# Sheet2.net
KiCad netlist of a schematic drawn in Altium Designer
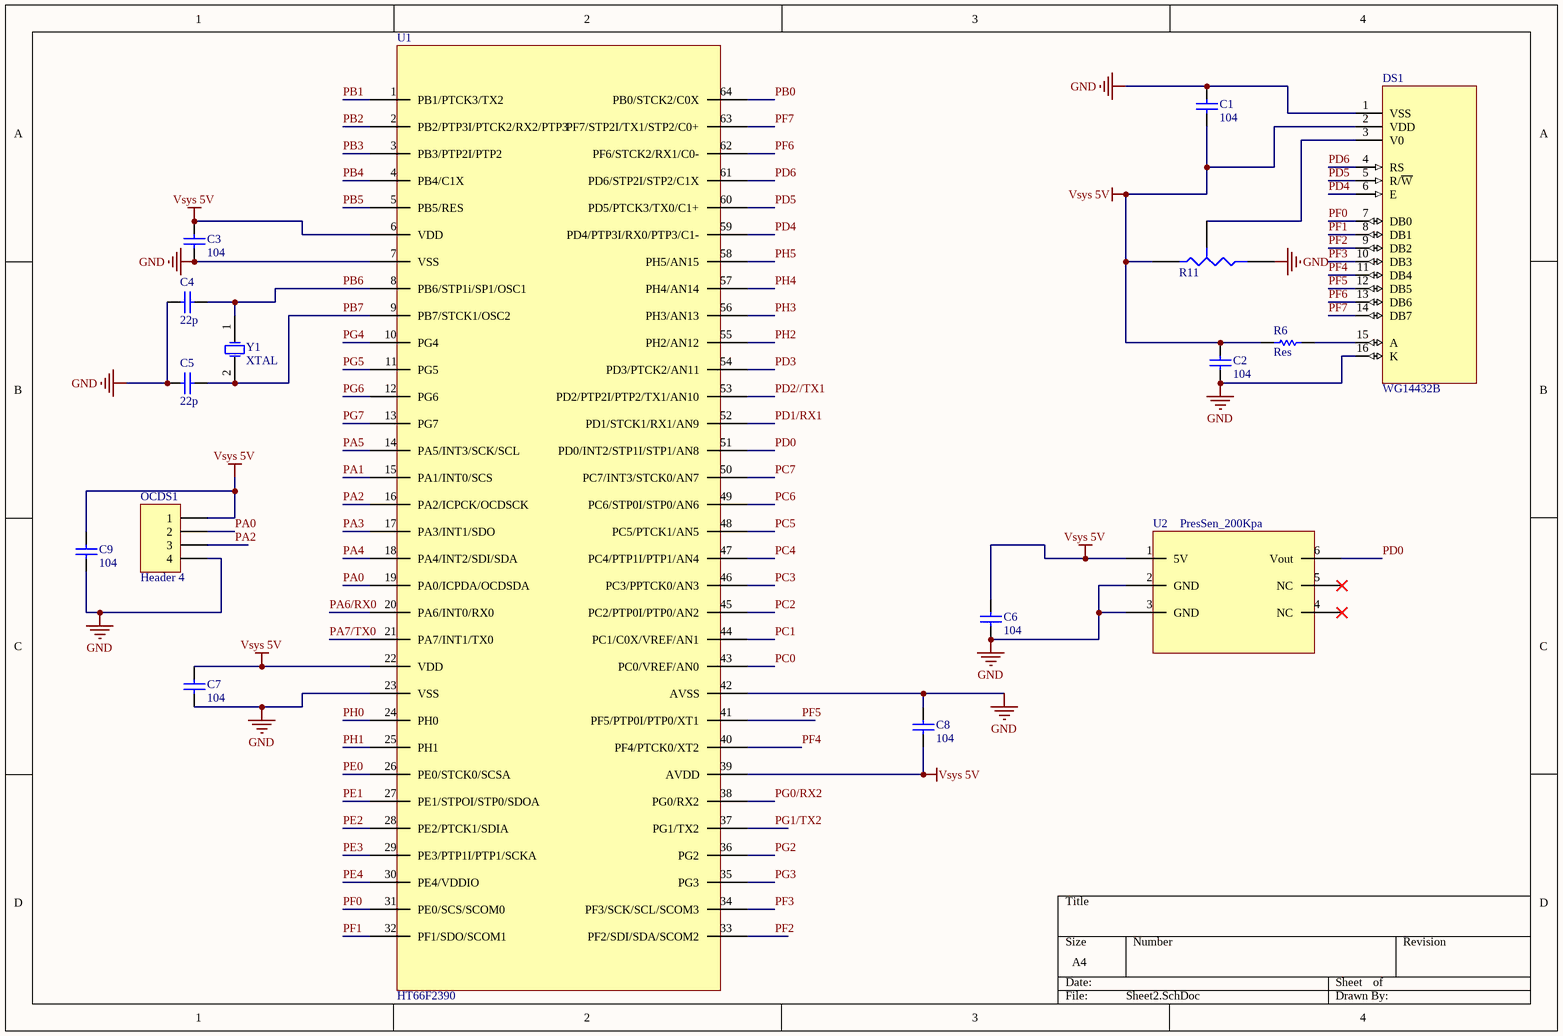
[diagram p0: Sheet2.SchDoc]

(export (version "E")
  (design (tool "Eeschema 10.0.6"))
  (components
    (comp (ref "C1")
      (value "104")
      (footprint "C200")
      (description "Capacitor")
      (fields (field (name "PUBLISHER") "Altium Limited"))
      (libsource (lib "myLib2009") (part "Cap"))
    )
    (comp (ref "C2")
      (value "104")
      (footprint "C200")
      (description "Capacitor")
      (fields (field (name "PUBLISHER") "Altium Limited"))
      (libsource (lib "myLib2009") (part "Cap"))
    )
    (comp (ref "C3")
      (value "104")
      (footprint "C200")
      (description "Capacitor")
      (fields (field (name "PUBLISHER") "Altium Limited"))
      (libsource (lib "myLib2009") (part "Cap"))
    )
    (comp (ref "C4")
      (value "22p")
      (footprint "C200")
      (description "Capacitor")
      (fields (field (name "PUBLISHER") "Altium Limited"))
      (libsource (lib "myLib2009") (part "Cap"))
    )
    (comp (ref "C5")
      (value "22p")
      (footprint "C200")
      (description "Capacitor")
      (fields (field (name "PUBLISHER") "Altium Limited"))
      (libsource (lib "myLib2009") (part "Cap"))
    )
    (comp (ref "C6")
      (value "104")
      (footprint "C200")
      (description "Capacitor")
      (fields (field (name "PUBLISHER") "Altium Limited"))
      (libsource (lib "myLib2009") (part "Cap"))
    )
    (comp (ref "C7")
      (value "104")
      (footprint "C200")
      (description "Capacitor")
      (fields (field (name "PUBLISHER") "Altium Limited"))
      (libsource (lib "myLib2009") (part "Cap"))
    )
    (comp (ref "C8")
      (value "104")
      (footprint "C200")
      (description "Capacitor")
      (fields (field (name "PUBLISHER") "Altium Limited"))
      (libsource (lib "myLib2009") (part "Cap"))
    )
    (comp (ref "C9")
      (value "104")
      (footprint "C200")
      (description "Capacitor")
      (fields (field (name "PUBLISHER") "Altium Limited"))
      (libsource (lib "myLib2009") (part "Cap"))
    )
    (comp (ref "DS1")
      (value "WG14432B")
      (footprint "LCM_16")
      (description "LCD Module")
      (libsource (lib "myLib2009") (part "WG14432B"))
    )
    (comp (ref "OCDS1")
      (value "Header 4")
      (footprint "HDR1X4")
      (description "Header, 4-Pin")
      (fields (field (name "PUBLISHER") "Altium Limited"))
      (libsource (lib "Miscellaneous Connectors") (part "Header 4"))
    )
    (comp (ref "R6")
      (value "Res")
      (footprint "AXIAL-0.3")
      (description "Resistor")
      (fields (field (name "PUBLISHER") "Altium Limited"))
      (libsource (lib "myLib2009") (part "Res"))
    )
    (comp (ref "R11")
      (value "Res Tap")
      (footprint "VR3")
      (description "Tapped Resistor")
      (fields (field (name "PUBLISHER") "Altium Limited"))
      (libsource (lib "Miscellaneous Devices") (part "Res Tap"))
    )
    (comp (ref "U1") (value "HT66F2390") (footprint "LFPQ-64") (libsource (lib "0612") (part "HT66F2390")))
    (comp (ref "U2")
      (value "PresSen_200Kpa")
      (footprint "RSCM17100Kxxxx")
      (libsource (lib "0612") (part "PresSen_200Kpa"))
    )
    (comp (ref "Y1")
      (value "XTAL")
      (footprint "XTAL4-8")
      (description "Crystal Oscillator")
      (fields (field (name "PUBLISHER") "Altium Limited"))
      (libsource (lib "myLib2009") (part "XTAL"))
    )
  )
  (nets
    (net (code "1") (name "/PA0") (class "Default")
      (node (ref "OCDS1") (pin "2") (pinfunction "2_2") (pintype "passive"))
      (node (ref "U1") (pin "19") (pinfunction "PA0/ICPDA/OCDSDA_19") (pintype "passive"))
    )
    (net (code "2") (name "/PA1") (class "Default")
      (node (ref "U1") (pin "15") (pinfunction "PA1/INT0/SCS_15") (pintype "passive"))
    )
    (net (code "3") (name "/PA2") (class "Default")
      (node (ref "OCDS1") (pin "3") (pinfunction "3_3") (pintype "passive"))
      (node (ref "U1") (pin "16") (pinfunction "PA2/ICPCK/OCDSCK_16") (pintype "passive"))
    )
    (net (code "4") (name "/PA3") (class "Default")
      (node (ref "U1") (pin "17") (pinfunction "PA3/INT1/SDO_17") (pintype "passive"))
    )
    (net (code "5") (name "/PA4") (class "Default")
      (node (ref "U1") (pin "18") (pinfunction "PA4/INT2/SDI/SDA_18") (pintype "passive"))
    )
    (net (code "6") (name "/PA5") (class "Default")
      (node (ref "U1") (pin "14") (pinfunction "PA5/INT3/SCK/SCL_14") (pintype "passive"))
    )
    (net (code "7") (name "/PA6{slash}RX0") (class "Default")
      (node (ref "U1") (pin "20") (pinfunction "PA6/INT0/RX0_20") (pintype "passive"))
    )
    (net (code "8") (name "/PA7{slash}TX0") (class "Default")
      (node (ref "U1") (pin "21") (pinfunction "PA7/INT1/TX0_21") (pintype "passive"))
    )
    (net (code "9") (name "/PB0") (class "Default")
      (node (ref "U1") (pin "64") (pinfunction "PB0/STCK2/C0X_64") (pintype "passive"))
    )
    (net (code "10") (name "/PB1") (class "Default")
      (node (ref "U1") (pin "1") (pinfunction "PB1/PTCK3/TX2_1") (pintype "passive"))
    )
    (net (code "11") (name "/PB2") (class "Default")
      (node (ref "U1") (pin "2") (pinfunction "PB2/PTP3I/PTCK2/RX2/PTP3_2") (pintype "passive"))
    )
    (net (code "12") (name "/PB3") (class "Default")
      (node (ref "U1") (pin "3") (pinfunction "PB3/PTP2I/PTP2_3") (pintype "passive"))
    )
    (net (code "13") (name "/PB4") (class "Default")
      (node (ref "U1") (pin "4") (pinfunction "PB4/C1X_4") (pintype "passive"))
    )
    (net (code "14") (name "/PB5") (class "Default")
      (node (ref "U1") (pin "5") (pinfunction "PB5/RES_5") (pintype "passive"))
    )
    (net (code "15") (name "/PB6") (class "Default")
      (node (ref "C4") (pin "2") (pinfunction "2_2") (pintype "passive"))
      (node (ref "U1") (pin "8") (pinfunction "PB6/STP1i/SP1/OSC1_8") (pintype "passive"))
      (node (ref "Y1") (pin "1") (pinfunction "OSC1_1") (pintype "passive"))
    )
    (net (code "16") (name "/PB7") (class "Default")
      (node (ref "C5") (pin "2") (pinfunction "2_2") (pintype "passive"))
      (node (ref "U1") (pin "9") (pinfunction "PB7/STCK1/OSC2_9") (pintype "passive"))
      (node (ref "Y1") (pin "2") (pinfunction "OSC2_2") (pintype "passive"))
    )
    (net (code "17") (name "/PC0") (class "Default")
      (node (ref "U1") (pin "43") (pinfunction "PC0/VREF/AN0_43") (pintype "passive"))
    )
    (net (code "18") (name "/PC1") (class "Default")
      (node (ref "U1") (pin "44") (pinfunction "PC1/C0X/VREF/AN1_44") (pintype "passive"))
    )
    (net (code "19") (name "/PC2") (class "Default")
      (node (ref "U1") (pin "45") (pinfunction "PC2/PTP0I/PTP0/AN2_45") (pintype "passive"))
    )
    (net (code "20") (name "/PC3") (class "Default")
      (node (ref "U1") (pin "46") (pinfunction "PC3/PPTCK0/AN3_46") (pintype "passive"))
    )
    (net (code "21") (name "/PC4") (class "Default")
      (node (ref "U1") (pin "47") (pinfunction "PC4/PTP1I/PTP1/AN4_47") (pintype "passive"))
    )
    (net (code "22") (name "/PC5") (class "Default")
      (node (ref "U1") (pin "48") (pinfunction "PC5/PTCK1/AN5_48") (pintype "passive"))
    )
    (net (code "23") (name "/PC6") (class "Default")
      (node (ref "U1") (pin "49") (pinfunction "PC6/STP0I/STP0/AN6_49") (pintype "passive"))
    )
    (net (code "24") (name "/PC7") (class "Default")
      (node (ref "U1") (pin "50") (pinfunction "PC7/INT3/STCK0/AN7_50") (pintype "passive"))
    )
    (net (code "25") (name "/PD0") (class "Default")
      (node (ref "U1") (pin "51") (pinfunction "PD0/INT2/STP1I/STP1/AN8_51") (pintype "passive"))
      (node (ref "U2") (pin "6") (pinfunction "Vout_6") (pintype "passive"))
    )
    (net (code "26") (name "/PD1{slash}RX1") (class "Default")
      (node (ref "U1") (pin "52") (pinfunction "PD1/STCK1/RX1/AN9_52") (pintype "passive"))
    )
    (net (code "27") (name "/PD2{slash}{slash}TX1") (class "Default")
      (node (ref "U1") (pin "53") (pinfunction "PD2/PTP2I/PTP2/TX1/AN10_53") (pintype "passive"))
    )
    (net (code "28") (name "/PD3") (class "Default")
      (node (ref "U1") (pin "54") (pinfunction "PD3/PTCK2/AN11_54") (pintype "passive"))
    )
    (net (code "29") (name "/PD4") (class "Default")
      (node (ref "DS1") (pin "6") (pinfunction "E_6") (pintype "input"))
      (node (ref "U1") (pin "59") (pinfunction "PD4/PTP3I/RX0/PTP3/C1-_59") (pintype "passive"))
    )
    (net (code "30") (name "/PD5") (class "Default")
      (node (ref "DS1") (pin "5") (pinfunction "R/~{W}_5") (pintype "input"))
      (node (ref "U1") (pin "60") (pinfunction "PD5/PTCK3/TX0/C1+_60") (pintype "passive"))
    )
    (net (code "31") (name "/PD6") (class "Default")
      (node (ref "DS1") (pin "4") (pinfunction "RS_4") (pintype "input"))
      (node (ref "U1") (pin "61") (pinfunction "PD6/STP2I/STP2/C1X_61") (pintype "passive"))
    )
    (net (code "32") (name "/PE0") (class "Default")
      (node (ref "U1") (pin "26") (pinfunction "PE0/STCK0/SCSA_26") (pintype "passive"))
    )
    (net (code "33") (name "/PE1") (class "Default")
      (node (ref "U1") (pin "27") (pinfunction "PE1/STPOI/STP0/SDOA_27") (pintype "passive"))
    )
    (net (code "34") (name "/PE2") (class "Default")
      (node (ref "U1") (pin "28") (pinfunction "PE2/PTCK1/SDIA_28") (pintype "passive"))
    )
    (net (code "35") (name "/PE3") (class "Default")
      (node (ref "U1") (pin "29") (pinfunction "PE3/PTP1I/PTP1/SCKA_29") (pintype "passive"))
    )
    (net (code "36") (name "/PE4") (class "Default")
      (node (ref "U1") (pin "30") (pinfunction "PE4/VDDIO_30") (pintype "passive"))
    )
    (net (code "37") (name "/PF0") (class "Default")
      (node (ref "DS1") (pin "7") (pinfunction "DB0_7") (pintype "bidirectional"))
      (node (ref "U1") (pin "31") (pinfunction "PE0/SCS/SCOM0_31") (pintype "passive"))
    )
    (net (code "38") (name "/PF1") (class "Default")
      (node (ref "DS1") (pin "8") (pinfunction "DB1_8") (pintype "bidirectional"))
      (node (ref "U1") (pin "32") (pinfunction "PF1/SDO/SCOM1_32") (pintype "passive"))
    )
    (net (code "39") (name "/PF2") (class "Default")
      (node (ref "DS1") (pin "9") (pinfunction "DB2_9") (pintype "bidirectional"))
      (node (ref "U1") (pin "33") (pinfunction "PF2/SDI/SDA/SCOM2_33") (pintype "passive"))
    )
    (net (code "40") (name "/PF3") (class "Default")
      (node (ref "DS1") (pin "10") (pinfunction "DB3_10") (pintype "bidirectional"))
      (node (ref "U1") (pin "34") (pinfunction "PF3/SCK/SCL/SCOM3_34") (pintype "passive"))
    )
    (net (code "41") (name "/PF4") (class "Default")
      (node (ref "DS1") (pin "11") (pinfunction "DB4_11") (pintype "bidirectional"))
      (node (ref "U1") (pin "40") (pinfunction "PF4/PTCK0/XT2_40") (pintype "passive"))
    )
    (net (code "42") (name "/PF5") (class "Default")
      (node (ref "DS1") (pin "12") (pinfunction "DB5_12") (pintype "bidirectional"))
      (node (ref "U1") (pin "41") (pinfunction "PF5/PTP0I/PTP0/XT1_41") (pintype "passive"))
    )
    (net (code "43") (name "/PF6") (class "Default")
      (node (ref "DS1") (pin "13") (pinfunction "DB6_13") (pintype "bidirectional"))
      (node (ref "U1") (pin "62") (pinfunction "PF6/STCK2/RX1/C0-_62") (pintype "passive"))
    )
    (net (code "44") (name "/PF7") (class "Default")
      (node (ref "DS1") (pin "14") (pinfunction "DB7_14") (pintype "bidirectional"))
      (node (ref "U1") (pin "63") (pinfunction "PF7/STP2I/TX1/STP2/C0+_63") (pintype "passive"))
    )
    (net (code "45") (name "/PG0{slash}RX2") (class "Default")
      (node (ref "U1") (pin "38") (pinfunction "PG0/RX2_38") (pintype "passive"))
    )
    (net (code "46") (name "/PG1{slash}TX2") (class "Default")
      (node (ref "U1") (pin "37") (pinfunction "PG1/TX2_37") (pintype "passive"))
    )
    (net (code "47") (name "/PG2") (class "Default")
      (node (ref "U1") (pin "36") (pinfunction "PG2_36") (pintype "passive"))
    )
    (net (code "48") (name "/PG3") (class "Default")
      (node (ref "U1") (pin "35") (pinfunction "PG3_35") (pintype "passive"))
    )
    (net (code "49") (name "/PG4") (class "Default")
      (node (ref "U1") (pin "10") (pinfunction "PG4_10") (pintype "passive"))
    )
    (net (code "50") (name "/PG5") (class "Default")
      (node (ref "U1") (pin "11") (pinfunction "PG5_11") (pintype "passive"))
    )
    (net (code "51") (name "/PG6") (class "Default")
      (node (ref "U1") (pin "12") (pinfunction "PG6_12") (pintype "passive"))
    )
    (net (code "52") (name "/PG7") (class "Default")
      (node (ref "U1") (pin "13") (pinfunction "PG7_13") (pintype "passive"))
    )
    (net (code "53") (name "/PH0") (class "Default")
      (node (ref "U1") (pin "24") (pinfunction "PH0_24") (pintype "passive"))
    )
    (net (code "54") (name "/PH1") (class "Default")
      (node (ref "U1") (pin "25") (pinfunction "PH1_25") (pintype "passive"))
    )
    (net (code "55") (name "/PH2") (class "Default")
      (node (ref "U1") (pin "55") (pinfunction "PH2/AN12_55") (pintype "passive"))
    )
    (net (code "56") (name "/PH3") (class "Default")
      (node (ref "U1") (pin "56") (pinfunction "PH3/AN13_56") (pintype "passive"))
    )
    (net (code "57") (name "/PH4") (class "Default")
      (node (ref "U1") (pin "57") (pinfunction "PH4/AN14_57") (pintype "passive"))
    )
    (net (code "58") (name "/PH5") (class "Default")
      (node (ref "U1") (pin "58") (pinfunction "PH5/AN15_58") (pintype "passive"))
    )
    (net (code "59") (name "GND") (class "Default")
      (node (ref "C1") (pin "2") (pinfunction "2_2") (pintype "passive"))
      (node (ref "C2") (pin "1") (pinfunction "1_1") (pintype "passive"))
      (node (ref "C3") (pin "1") (pinfunction "1_1") (pintype "passive"))
      (node (ref "C4") (pin "1") (pinfunction "1_1") (pintype "passive"))
      (node (ref "C5") (pin "1") (pinfunction "1_1") (pintype "passive"))
      (node (ref "C6") (pin "1") (pinfunction "1_1") (pintype "passive"))
      (node (ref "C7") (pin "1") (pinfunction "1_1") (pintype "passive"))
      (node (ref "C8") (pin "2") (pinfunction "2_2") (pintype "passive"))
      (node (ref "C9") (pin "1") (pinfunction "1_1") (pintype "passive"))
      (node (ref "DS1") (pin "1") (pinfunction "VSS_1") (pintype "passive"))
      (node (ref "DS1") (pin "16") (pinfunction "K_16") (pintype "bidirectional"))
      (node (ref "OCDS1") (pin "4") (pinfunction "4_4") (pintype "passive"))
      (node (ref "R11") (pin "2") (pinfunction "B_2") (pintype "passive"))
      (node (ref "U1") (pin "23") (pinfunction "VSS_23") (pintype "passive"))
      (node (ref "U1") (pin "42") (pinfunction "AVSS_42") (pintype "passive"))
      (node (ref "U1") (pin "7") (pinfunction "VSS_7") (pintype "passive"))
      (node (ref "U2") (pin "2") (pinfunction "GND_2") (pintype "passive"))
      (node (ref "U2") (pin "3") (pinfunction "GND_3") (pintype "passive"))
    )
    (net (code "60") (name "Net-(DS1-A)") (class "Default")
      (node (ref "DS1") (pin "15") (pinfunction "A_15") (pintype "bidirectional"))
      (node (ref "R6") (pin "2") (pinfunction "2_2") (pintype "passive"))
    )
    (net (code "61") (name "Net-(DS1-V0)") (class "Default")
      (node (ref "DS1") (pin "3") (pinfunction "V0_3") (pintype "passive"))
      (node (ref "R11") (pin "3") (pinfunction "TAP_3") (pintype "passive"))
    )
    (net (code "62") (name "Vsys 5V") (class "Default")
      (node (ref "C1") (pin "1") (pinfunction "1_1") (pintype "passive"))
      (node (ref "C2") (pin "2") (pinfunction "2_2") (pintype "passive"))
      (node (ref "C3") (pin "2") (pinfunction "2_2") (pintype "passive"))
      (node (ref "C6") (pin "2") (pinfunction "2_2") (pintype "passive"))
      (node (ref "C7") (pin "2") (pinfunction "2_2") (pintype "passive"))
      (node (ref "C8") (pin "1") (pinfunction "1_1") (pintype "passive"))
      (node (ref "C9") (pin "2") (pinfunction "2_2") (pintype "passive"))
      (node (ref "DS1") (pin "2") (pinfunction "VDD_2") (pintype "passive"))
      (node (ref "OCDS1") (pin "1") (pinfunction "1_1") (pintype "passive"))
      (node (ref "R11") (pin "1") (pinfunction "A_1") (pintype "passive"))
      (node (ref "R6") (pin "1") (pinfunction "1_1") (pintype "passive"))
      (node (ref "U1") (pin "22") (pinfunction "VDD_22") (pintype "passive"))
      (node (ref "U1") (pin "39") (pinfunction "AVDD_39") (pintype "passive"))
      (node (ref "U1") (pin "6") (pinfunction "VDD_6") (pintype "passive"))
      (node (ref "U2") (pin "1") (pinfunction "5V_1") (pintype "passive"))
    )
    (net (code "63") (name "unconnected-(U2-NC-Pad4)") (class "Default")
      (node (ref "U2") (pin "4") (pinfunction "NC_4") (pintype "passive+no_connect"))
    )
    (net (code "64") (name "unconnected-(U2-NC-Pad5)") (class "Default")
      (node (ref "U2") (pin "5") (pinfunction "NC_5") (pintype "passive+no_connect"))
    )
  )
)
